# marquee-letter.net
KiCad netlist of a schematic drawn in EAGLE
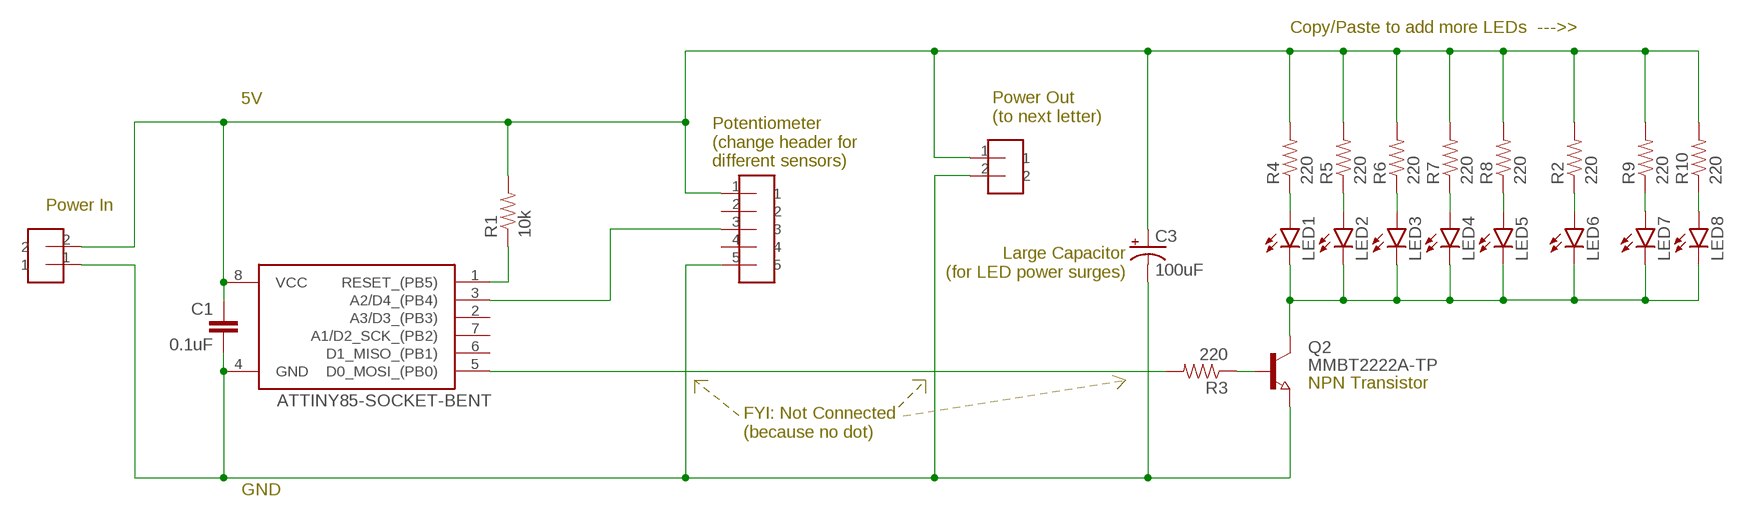
[diagram p0: schematic, sheet 1]

(export (version "E")
  (design (tool "Eeschema 10.0.6"))
  (components
    (comp (ref "C1")
      (value "0.1uF")
      (footprint "eagle-import:0805")
      (libsource (lib "eagle-import") (part "CAP-0805"))
    )
    (comp (ref "C3")
      (value "100uF")
      (footprint "eagle-import:PANASONIC_D")
      (libsource (lib "eagle-import") (part "CAP_POLD"))
    )
    (comp (ref "LED1")
      (value "LED0603")
      (footprint "eagle-import:LED-0603")
      (libsource (lib "eagle-import") (part "LED0603"))
    )
    (comp (ref "LED2")
      (value "LED0603")
      (footprint "eagle-import:LED-0603")
      (libsource (lib "eagle-import") (part "LED0603"))
    )
    (comp (ref "LED3")
      (value "LED0603")
      (footprint "eagle-import:LED-0603")
      (libsource (lib "eagle-import") (part "LED0603"))
    )
    (comp (ref "LED4")
      (value "LED0603")
      (footprint "eagle-import:LED-0603")
      (libsource (lib "eagle-import") (part "LED0603"))
    )
    (comp (ref "LED5")
      (value "LED0603")
      (footprint "eagle-import:LED-0603")
      (libsource (lib "eagle-import") (part "LED0603"))
    )
    (comp (ref "LED6")
      (value "LED0603")
      (footprint "eagle-import:LED-0603")
      (libsource (lib "eagle-import") (part "LED0603"))
    )
    (comp (ref "LED7")
      (value "LED0603")
      (footprint "eagle-import:LED-0603")
      (libsource (lib "eagle-import") (part "LED0603"))
    )
    (comp (ref "LED8")
      (value "LED0603")
      (footprint "eagle-import:LED-0603")
      (libsource (lib "eagle-import") (part "LED0603"))
    )
    (comp (ref "POTENTIOMETER")
      (value "HEADER-5")
      (footprint "eagle-import:HEADER-5")
      (libsource (lib "eagle-import") (part "HEADER-5"))
    )
    (comp (ref "Q2")
      (value "MMBT2222A-TP")
      (footprint "eagle-import:SOT23")
      (libsource (lib "eagle-import") (part "TRANSISTOR-NPN-SOT23"))
    )
    (comp (ref "R1")
      (value "10k")
      (footprint "eagle-import:0805")
      (libsource (lib "eagle-import") (part "RESISTOR-0805"))
    )
    (comp (ref "R2")
      (value "220")
      (footprint "eagle-import:0603-RES")
      (libsource (lib "eagle-import") (part "RESISTOR0603"))
    )
    (comp (ref "R3")
      (value "220")
      (footprint "eagle-import:0805")
      (libsource (lib "eagle-import") (part "RESISTOR-0805"))
    )
    (comp (ref "R4")
      (value "220")
      (footprint "eagle-import:0603-RES")
      (libsource (lib "eagle-import") (part "RESISTOR0603"))
    )
    (comp (ref "R5")
      (value "220")
      (footprint "eagle-import:0603-RES")
      (libsource (lib "eagle-import") (part "RESISTOR0603"))
    )
    (comp (ref "R6")
      (value "220")
      (footprint "eagle-import:0603-RES")
      (libsource (lib "eagle-import") (part "RESISTOR0603"))
    )
    (comp (ref "R7")
      (value "220")
      (footprint "eagle-import:0603-RES")
      (libsource (lib "eagle-import") (part "RESISTOR0603"))
    )
    (comp (ref "R8")
      (value "220")
      (footprint "eagle-import:0603-RES")
      (libsource (lib "eagle-import") (part "RESISTOR0603"))
    )
    (comp (ref "R9")
      (value "220")
      (footprint "eagle-import:0603-RES")
      (libsource (lib "eagle-import") (part "RESISTOR0603"))
    )
    (comp (ref "R10")
      (value "220")
      (footprint "eagle-import:0603-RES")
      (libsource (lib "eagle-import") (part "RESISTOR0603"))
    )
    (comp (ref "U$1")
      (value "ATTINY85-SOCKET-BENT")
      (footprint "eagle-import:SOCKET-8PIN-BENT")
      (libsource (lib "eagle-import") (part "ATTINY85-SOCKET-BENT"))
    )
    (comp (ref "U$2")
      (value "HEADER-2")
      (footprint "eagle-import:HEADER-2")
      (libsource (lib "eagle-import") (part "HEADER-2"))
    )
    (comp (ref "U$3")
      (value "HEADER-2")
      (footprint "eagle-import:HEADER-2")
      (libsource (lib "eagle-import") (part "HEADER-2"))
    )
  )
  (nets
    (net (code "1") (name "Net-(LED1-PadA)") (class "Default")
      (node (ref "LED1") (pin "A") (pinfunction "A_A") (pintype "passive"))
      (node (ref "R4") (pin "1") (pinfunction "1_1") (pintype "passive"))
    )
    (net (code "2") (name "Net-(LED2-PadA)") (class "Default")
      (node (ref "LED2") (pin "A") (pinfunction "A_A") (pintype "passive"))
      (node (ref "R5") (pin "1") (pinfunction "1_1") (pintype "passive"))
    )
    (net (code "3") (name "Net-(LED3-PadA)") (class "Default")
      (node (ref "LED3") (pin "A") (pinfunction "A_A") (pintype "passive"))
      (node (ref "R6") (pin "1") (pinfunction "1_1") (pintype "passive"))
    )
    (net (code "4") (name "Net-(LED4-PadA)") (class "Default")
      (node (ref "LED4") (pin "A") (pinfunction "A_A") (pintype "passive"))
      (node (ref "R7") (pin "1") (pinfunction "1_1") (pintype "passive"))
    )
    (net (code "5") (name "Net-(LED5-PadA)") (class "Default")
      (node (ref "LED5") (pin "A") (pinfunction "A_A") (pintype "passive"))
      (node (ref "R8") (pin "1") (pinfunction "1_1") (pintype "passive"))
    )
    (net (code "6") (name "Net-(LED6-PadA)") (class "Default")
      (node (ref "LED6") (pin "A") (pinfunction "A_A") (pintype "passive"))
      (node (ref "R2") (pin "1") (pinfunction "1_1") (pintype "passive"))
    )
    (net (code "7") (name "Net-(LED7-PadA)") (class "Default")
      (node (ref "LED7") (pin "A") (pinfunction "A_A") (pintype "passive"))
      (node (ref "R9") (pin "1") (pinfunction "1_1") (pintype "passive"))
    )
    (net (code "8") (name "Net-(LED8-PadA)") (class "Default")
      (node (ref "LED8") (pin "A") (pinfunction "A_A") (pintype "passive"))
      (node (ref "R10") (pin "1") (pinfunction "1_1") (pintype "passive"))
    )
    (net (code "9") (name "Net-(Q2-B)") (class "Default")
      (node (ref "Q2") (pin "1") (pinfunction "B_1") (pintype "passive"))
      (node (ref "R3") (pin "1") (pinfunction "1_1") (pintype "passive"))
    )
    (net (code "10") (name "Net-(Q2-C)") (class "Default")
      (node (ref "LED1") (pin "C") (pinfunction "C_C") (pintype "passive"))
      (node (ref "LED2") (pin "C") (pinfunction "C_C") (pintype "passive"))
      (node (ref "LED3") (pin "C") (pinfunction "C_C") (pintype "passive"))
      (node (ref "LED4") (pin "C") (pinfunction "C_C") (pintype "passive"))
      (node (ref "LED5") (pin "C") (pinfunction "C_C") (pintype "passive"))
      (node (ref "LED6") (pin "C") (pinfunction "C_C") (pintype "passive"))
      (node (ref "LED7") (pin "C") (pinfunction "C_C") (pintype "passive"))
      (node (ref "LED8") (pin "C") (pinfunction "C_C") (pintype "passive"))
      (node (ref "Q2") (pin "3") (pinfunction "C_3") (pintype "passive"))
    )
    (net (code "11") (name "Net-(Q2-E)") (class "Default")
      (node (ref "C1") (pin "2") (pinfunction "2_2") (pintype "passive"))
      (node (ref "C3") (pin "-") (pinfunction "-_-") (pintype "passive"))
      (node (ref "POTENTIOMETER") (pin "5") (pinfunction "5_5") (pintype "bidirectional"))
      (node (ref "Q2") (pin "2") (pinfunction "E_2") (pintype "passive"))
      (node (ref "U$1") (pin "4") (pinfunction "GND_4") (pintype "power_in"))
      (node (ref "U$2") (pin "1") (pinfunction "1_1") (pintype "bidirectional"))
      (node (ref "U$3") (pin "2") (pinfunction "2_2") (pintype "bidirectional"))
    )
    (net (code "12") (name "Net-(U$1-A2{slash}D4_(PB4))") (class "Default")
      (node (ref "POTENTIOMETER") (pin "3") (pinfunction "3_3") (pintype "bidirectional"))
      (node (ref "U$1") (pin "3") (pinfunction "A2/D4_(PB4)_3") (pintype "bidirectional"))
    )
    (net (code "13") (name "Net-(U$1-D0_MOSI_(PB0))") (class "Default")
      (node (ref "R3") (pin "2") (pinfunction "2_2") (pintype "passive"))
      (node (ref "U$1") (pin "5") (pinfunction "D0_MOSI_(PB0)_5") (pintype "bidirectional"))
    )
    (net (code "14") (name "Net-(U$1-RESET_(PB5))") (class "Default")
      (node (ref "R1") (pin "1") (pinfunction "1_1") (pintype "passive"))
      (node (ref "U$1") (pin "1") (pinfunction "RESET_(PB5)_1") (pintype "bidirectional"))
    )
    (net (code "15") (name "Net-(U$1-VCC)") (class "Default")
      (node (ref "C1") (pin "1") (pinfunction "1_1") (pintype "passive"))
      (node (ref "C3") (pin "+") (pinfunction "+_+") (pintype "passive"))
      (node (ref "POTENTIOMETER") (pin "1") (pinfunction "1_1") (pintype "bidirectional"))
      (node (ref "R1") (pin "2") (pinfunction "2_2") (pintype "passive"))
      (node (ref "R10") (pin "2") (pinfunction "2_2") (pintype "passive"))
      (node (ref "R2") (pin "2") (pinfunction "2_2") (pintype "passive"))
      (node (ref "R4") (pin "2") (pinfunction "2_2") (pintype "passive"))
      (node (ref "R5") (pin "2") (pinfunction "2_2") (pintype "passive"))
      (node (ref "R6") (pin "2") (pinfunction "2_2") (pintype "passive"))
      (node (ref "R7") (pin "2") (pinfunction "2_2") (pintype "passive"))
      (node (ref "R8") (pin "2") (pinfunction "2_2") (pintype "passive"))
      (node (ref "R9") (pin "2") (pinfunction "2_2") (pintype "passive"))
      (node (ref "U$1") (pin "8") (pinfunction "VCC_8") (pintype "power_in"))
      (node (ref "U$2") (pin "2") (pinfunction "2_2") (pintype "bidirectional"))
      (node (ref "U$3") (pin "1") (pinfunction "1_1") (pintype "bidirectional"))
    )
    (net (code "16") (name "unconnected-(POTENTIOMETER-Pad2)") (class "Default")
      (node (ref "POTENTIOMETER") (pin "2") (pinfunction "2_2") (pintype "bidirectional"))
    )
    (net (code "17") (name "unconnected-(POTENTIOMETER-Pad4)") (class "Default")
      (node (ref "POTENTIOMETER") (pin "4") (pinfunction "4_4") (pintype "bidirectional"))
    )
    (net (code "18") (name "unconnected-(U$1-A1{slash}D2_SCK_(PB2)-Pad7)") (class "Default")
      (node (ref "U$1") (pin "7") (pinfunction "A1/D2_SCK_(PB2)_7") (pintype "bidirectional"))
    )
    (net (code "19") (name "unconnected-(U$1-A3{slash}D3_(PB3)-Pad2)") (class "Default")
      (node (ref "U$1") (pin "2") (pinfunction "A3/D3_(PB3)_2") (pintype "bidirectional"))
    )
    (net (code "20") (name "unconnected-(U$1-D1_MISO_(PB1)-Pad6)") (class "Default")
      (node (ref "U$1") (pin "6") (pinfunction "D1_MISO_(PB1)_6") (pintype "bidirectional"))
    )
  )
)
